# BottomBoard_Imu_Arduinio.net
KiCad netlist of a schematic drawn in EAGLE
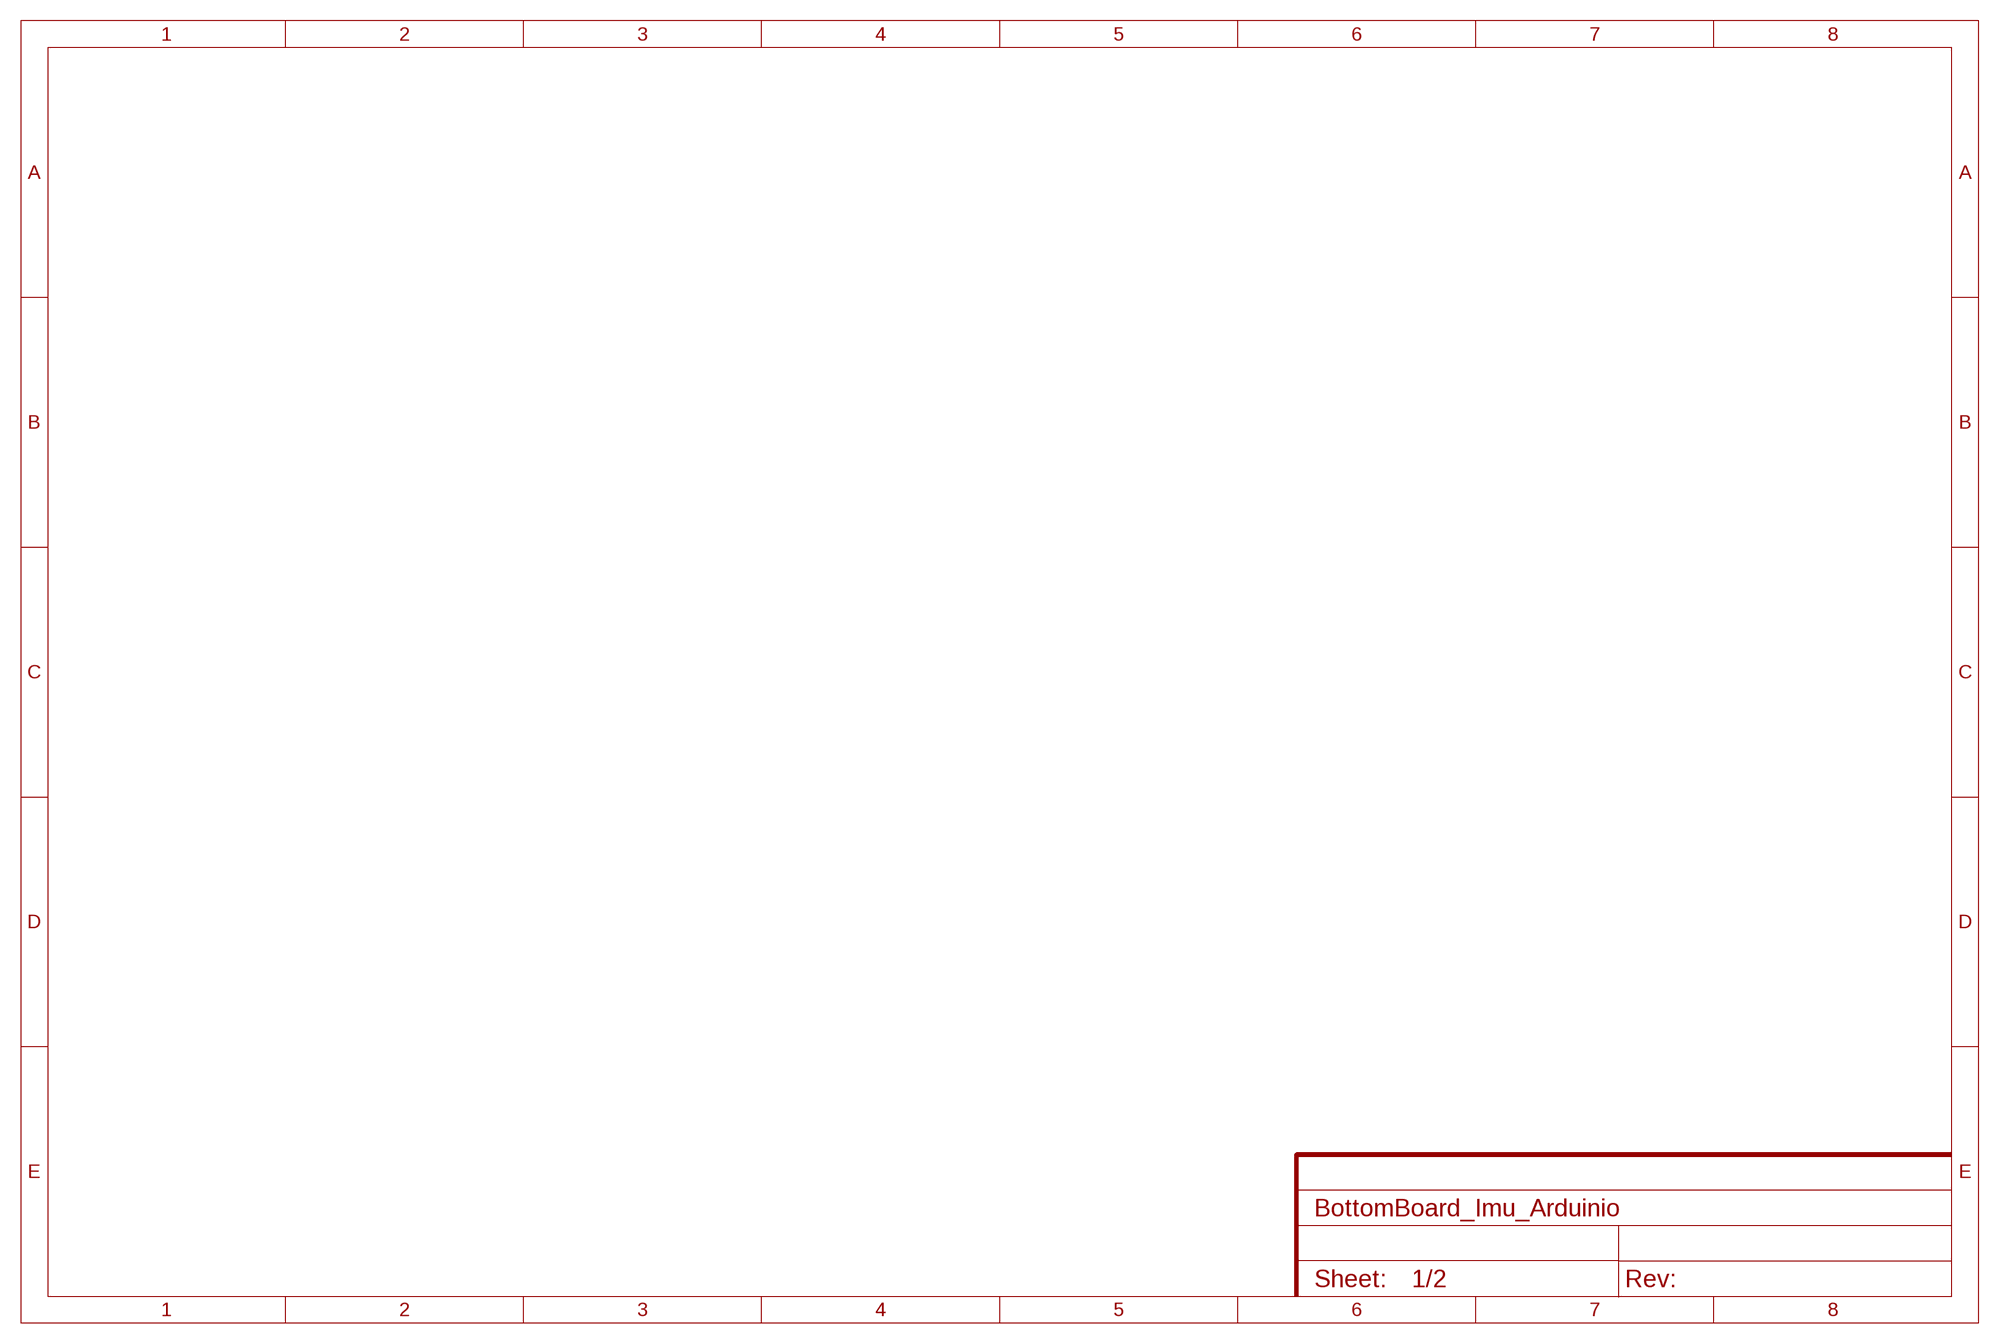
[diagram p0: schematic, sheet 1]
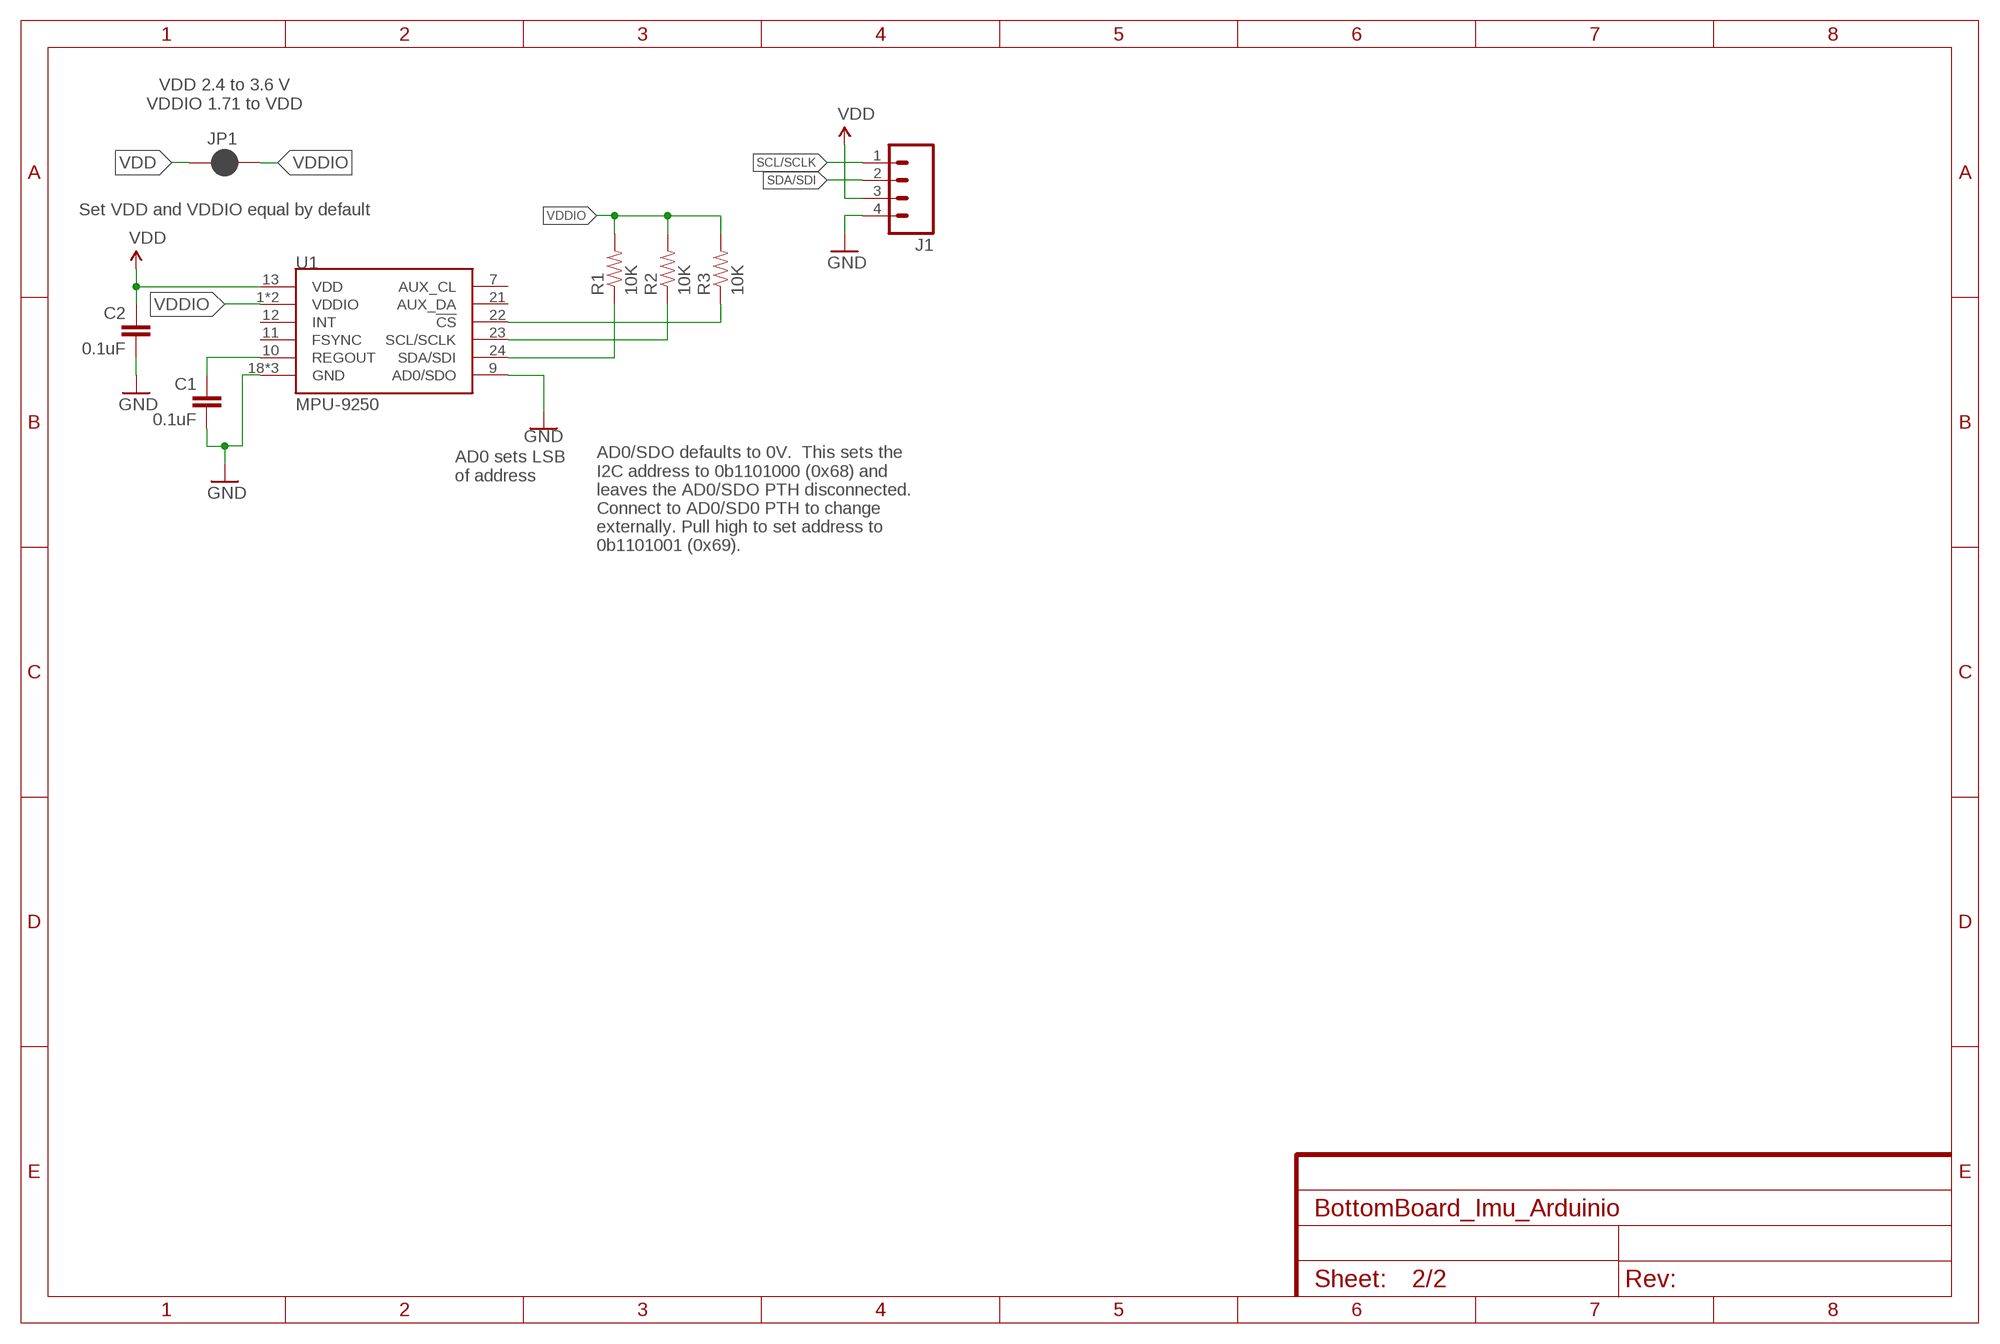
[diagram p1: schematic, sheet 2]

(export (version "E")
  (design (tool "Eeschema 10.0.6"))
  (components
    (comp (ref "C1")
      (value "0.1uF")
      (footprint "eagle-import:0603-CAP")
      (libsource (lib "eagle-import") (part "0.1UF-25V(+80/-20%)(0603)"))
    )
    (comp (ref "C2")
      (value "0.1uF")
      (footprint "eagle-import:0603-CAP")
      (libsource (lib "eagle-import") (part "0.1UF-25V(+80/-20%)(0603)"))
    )
    (comp (ref "J1")
      (value "M04PTH")
      (footprint "eagle-import:1X04")
      (libsource (lib "eagle-import") (part "M04PTH"))
    )
    (comp (ref "JP1")
      (value "JUMPER-SMT_2_NC_PASTE_NO-SILK")
      (footprint "eagle-import:SMT-JUMPER_2_NC_PASTE_NO-SILK")
      (libsource (lib "eagle-import") (part "JUMPER-SMT_2_NC_PASTE_NO-SILK"))
    )
    (comp (ref "R1")
      (value "10K")
      (footprint "eagle-import:0603-RES")
      (libsource (lib "eagle-import") (part "10KOHM-1/10W-1%(0603)0603"))
    )
    (comp (ref "R2")
      (value "10K")
      (footprint "eagle-import:0603-RES")
      (libsource (lib "eagle-import") (part "10KOHM-1/10W-1%(0603)0603"))
    )
    (comp (ref "R3")
      (value "10K")
      (footprint "eagle-import:0603-RES")
      (libsource (lib "eagle-import") (part "10KOHM-1/10W-1%(0603)0603"))
    )
    (comp (ref "U1")
      (value "MPU-9250")
      (footprint "eagle-import:QFN24_PAD")
      (libsource (lib "eagle-import") (part "MPU-9250"))
    )
  )
  (nets
    (net (code "1") (name "GND") (class "Default")
      (node (ref "C1") (pin "2") (pinfunction "2_2") (pintype "passive"))
      (node (ref "C2") (pin "2") (pinfunction "2_2") (pintype "passive"))
      (node (ref "J1") (pin "4") (pinfunction "4_4") (pintype "passive"))
      (node (ref "U1") (pin "18") (pinfunction "GND_18") (pintype "bidirectional"))
      (node (ref "U1") (pin "20") (pinfunction "GND_20") (pintype "bidirectional"))
      (node (ref "U1") (pin "9") (pinfunction "AD0/SDO_9") (pintype "bidirectional"))
      (node (ref "U1") (pin "CENTER") (pinfunction "GND_CENTER") (pintype "bidirectional"))
    )
    (net (code "2") (name "Net-(U1-REGOUT)") (class "Default")
      (node (ref "C1") (pin "1") (pinfunction "1_1") (pintype "passive"))
      (node (ref "U1") (pin "10") (pinfunction "REGOUT_10") (pintype "bidirectional"))
    )
    (net (code "3") (name "Net-(U1-~{CS})") (class "Default")
      (node (ref "R3") (pin "1") (pinfunction "1_1") (pintype "passive"))
      (node (ref "U1") (pin "22") (pinfunction "~{CS}_22") (pintype "bidirectional"))
    )
    (net (code "4") (name "SCL{slash}SCLK") (class "Default")
      (node (ref "J1") (pin "1") (pinfunction "1_1") (pintype "passive"))
      (node (ref "R2") (pin "1") (pinfunction "1_1") (pintype "passive"))
      (node (ref "U1") (pin "23") (pinfunction "SCL/SCLK_23") (pintype "bidirectional"))
    )
    (net (code "5") (name "SDA{slash}SDI") (class "Default")
      (node (ref "J1") (pin "2") (pinfunction "2_2") (pintype "passive"))
      (node (ref "R1") (pin "1") (pinfunction "1_1") (pintype "passive"))
      (node (ref "U1") (pin "24") (pinfunction "SDA/SDI_24") (pintype "bidirectional"))
    )
    (net (code "6") (name "VDD") (class "Default")
      (node (ref "C2") (pin "1") (pinfunction "1_1") (pintype "passive"))
      (node (ref "J1") (pin "3") (pinfunction "3_3") (pintype "passive"))
      (node (ref "JP1") (pin "1") (pinfunction "1_1") (pintype "passive"))
      (node (ref "U1") (pin "13") (pinfunction "VDD_13") (pintype "bidirectional"))
    )
    (net (code "7") (name "VDDIO") (class "Default")
      (node (ref "JP1") (pin "2") (pinfunction "2_2") (pintype "passive"))
      (node (ref "R1") (pin "2") (pinfunction "2_2") (pintype "passive"))
      (node (ref "R2") (pin "2") (pinfunction "2_2") (pintype "passive"))
      (node (ref "R3") (pin "2") (pinfunction "2_2") (pintype "passive"))
      (node (ref "U1") (pin "1") (pinfunction "VDDIO_1") (pintype "bidirectional"))
      (node (ref "U1") (pin "8") (pinfunction "VDDIO_8") (pintype "bidirectional"))
    )
    (net (code "8") (name "unconnected-(U1-AUX_CL-Pad7)") (class "Default")
      (node (ref "U1") (pin "7") (pinfunction "AUX_CL_7") (pintype "bidirectional"))
    )
    (net (code "9") (name "unconnected-(U1-AUX_DA-Pad21)") (class "Default")
      (node (ref "U1") (pin "21") (pinfunction "AUX_DA_21") (pintype "bidirectional"))
    )
    (net (code "10") (name "unconnected-(U1-FSYNC-Pad11)") (class "Default")
      (node (ref "U1") (pin "11") (pinfunction "FSYNC_11") (pintype "bidirectional"))
    )
    (net (code "11") (name "unconnected-(U1-INT-Pad12)") (class "Default")
      (node (ref "U1") (pin "12") (pinfunction "INT_12") (pintype "bidirectional"))
    )
  )
)
